# Peripherals.net
KiCad netlist of a schematic drawn in Altium Designer
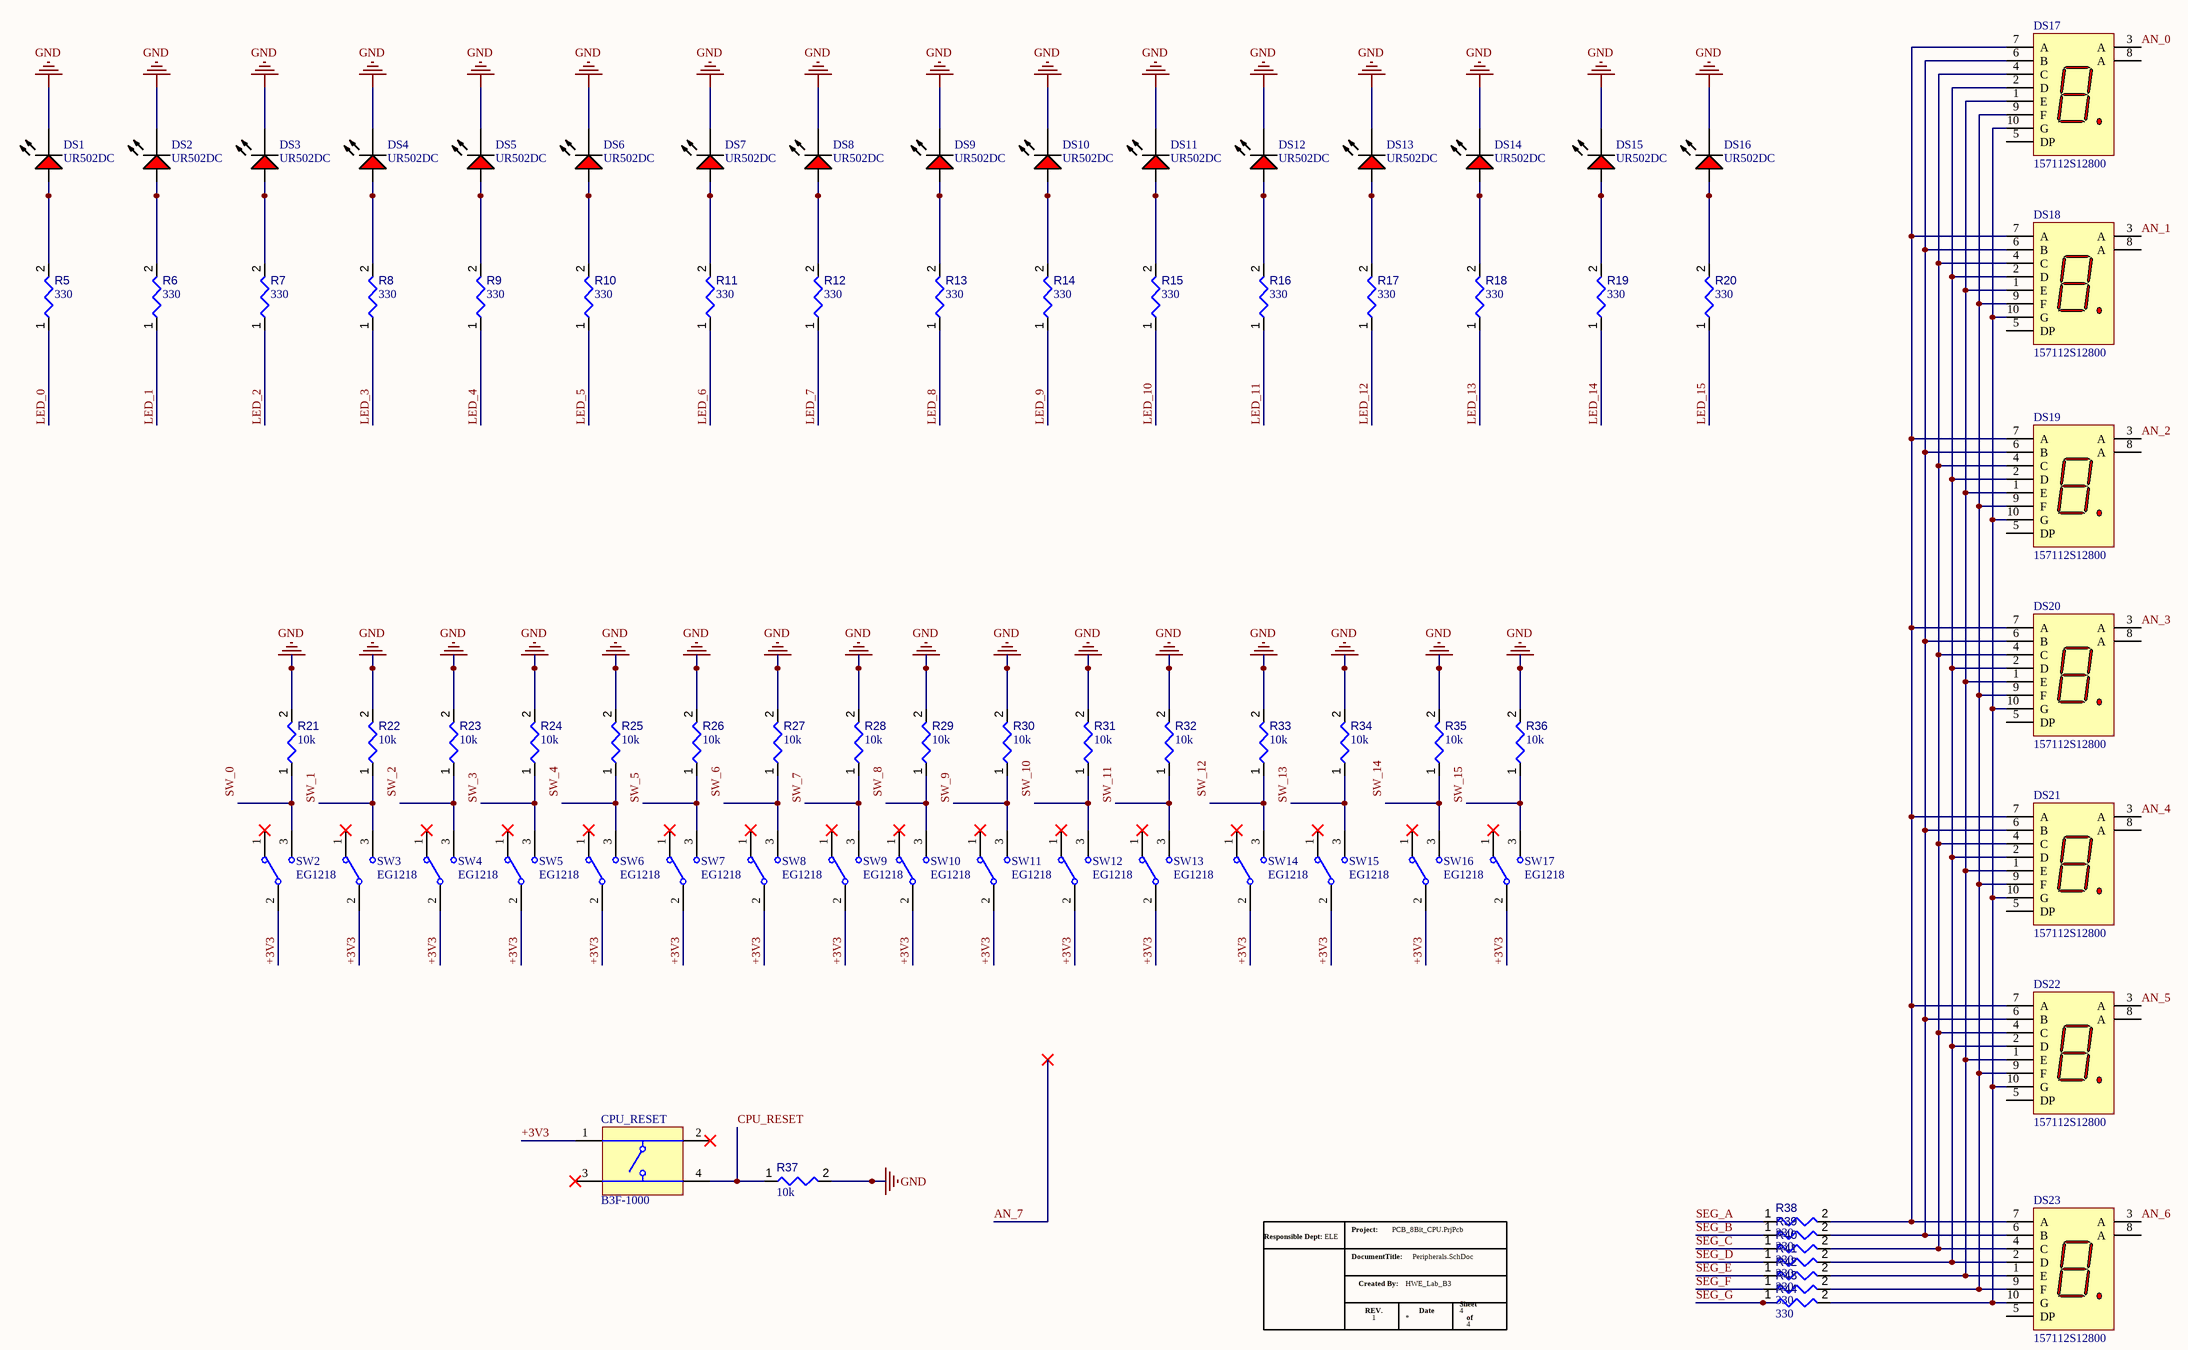
[diagram p0: Peripherals.SchDoc]

(export (version "E")
  (design (tool "Eeschema 10.0.6"))
  (components
    (comp (ref "CPU_RESET")
      (value "B3F-1000")
      (footprint "OMRON-B3F-1000-4_V")
      (description "Tactile Switch, SPST-NO, 0.05 A, 5 to 24 V, -25 to 70 degC, 4-Pin THD, RoHS, Bulk")
      (libsource (lib "Altium Content Vault") (part "SW-SPST-4_A"))
    )
    (comp (ref "DS1")
      (value "UR502DC")
      (footprint "CGX-UR502DC")
      (description "Red LED, 80 mW, 30 mA, -25 to 85 degC, 2-Pin THD")
      (fields (field (name "POWER") "80mW") (field (name "MANUFACTURER") "Shenzhen CGX"))
      (libsource (lib "MD RUHUL KUDDUS SALEH") (part "LED-RED-AK-2"))
    )
    (comp (ref "DS2")
      (value "UR502DC")
      (footprint "CGX-UR502DC")
      (description "Red LED, 80 mW, 30 mA, -25 to 85 degC, 2-Pin THD")
      (fields (field (name "POWER") "80mW") (field (name "MANUFACTURER") "Shenzhen CGX"))
      (libsource (lib "MD RUHUL KUDDUS SALEH") (part "LED-RED-AK-2"))
    )
    (comp (ref "DS3")
      (value "UR502DC")
      (footprint "CGX-UR502DC")
      (description "Red LED, 80 mW, 30 mA, -25 to 85 degC, 2-Pin THD")
      (fields (field (name "POWER") "80mW") (field (name "MANUFACTURER") "Shenzhen CGX"))
      (libsource (lib "MD RUHUL KUDDUS SALEH") (part "LED-RED-AK-2"))
    )
    (comp (ref "DS4")
      (value "UR502DC")
      (footprint "CGX-UR502DC")
      (description "Red LED, 80 mW, 30 mA, -25 to 85 degC, 2-Pin THD")
      (fields (field (name "POWER") "80mW") (field (name "MANUFACTURER") "Shenzhen CGX"))
      (libsource (lib "MD RUHUL KUDDUS SALEH") (part "LED-RED-AK-2"))
    )
    (comp (ref "DS5")
      (value "UR502DC")
      (footprint "CGX-UR502DC")
      (description "Red LED, 80 mW, 30 mA, -25 to 85 degC, 2-Pin THD")
      (fields (field (name "POWER") "80mW") (field (name "MANUFACTURER") "Shenzhen CGX"))
      (libsource (lib "MD RUHUL KUDDUS SALEH") (part "LED-RED-AK-2"))
    )
    (comp (ref "DS6")
      (value "UR502DC")
      (footprint "CGX-UR502DC")
      (description "Red LED, 80 mW, 30 mA, -25 to 85 degC, 2-Pin THD")
      (fields (field (name "POWER") "80mW") (field (name "MANUFACTURER") "Shenzhen CGX"))
      (libsource (lib "MD RUHUL KUDDUS SALEH") (part "LED-RED-AK-2"))
    )
    (comp (ref "DS7")
      (value "UR502DC")
      (footprint "CGX-UR502DC")
      (description "Red LED, 80 mW, 30 mA, -25 to 85 degC, 2-Pin THD")
      (fields (field (name "POWER") "80mW") (field (name "MANUFACTURER") "Shenzhen CGX"))
      (libsource (lib "MD RUHUL KUDDUS SALEH") (part "LED-RED-AK-2"))
    )
    (comp (ref "DS8")
      (value "UR502DC")
      (footprint "CGX-UR502DC")
      (description "Red LED, 80 mW, 30 mA, -25 to 85 degC, 2-Pin THD")
      (fields (field (name "POWER") "80mW") (field (name "MANUFACTURER") "Shenzhen CGX"))
      (libsource (lib "MD RUHUL KUDDUS SALEH") (part "LED-RED-AK-2"))
    )
    (comp (ref "DS9")
      (value "UR502DC")
      (footprint "CGX-UR502DC")
      (description "Red LED, 80 mW, 30 mA, -25 to 85 degC, 2-Pin THD")
      (fields (field (name "POWER") "80mW") (field (name "MANUFACTURER") "Shenzhen CGX"))
      (libsource (lib "MD RUHUL KUDDUS SALEH") (part "LED-RED-AK-2"))
    )
    (comp (ref "DS10")
      (value "UR502DC")
      (footprint "CGX-UR502DC")
      (description "Red LED, 80 mW, 30 mA, -25 to 85 degC, 2-Pin THD")
      (fields (field (name "POWER") "80mW") (field (name "MANUFACTURER") "Shenzhen CGX"))
      (libsource (lib "MD RUHUL KUDDUS SALEH") (part "LED-RED-AK-2"))
    )
    (comp (ref "DS11")
      (value "UR502DC")
      (footprint "CGX-UR502DC")
      (description "Red LED, 80 mW, 30 mA, -25 to 85 degC, 2-Pin THD")
      (fields (field (name "POWER") "80mW") (field (name "MANUFACTURER") "Shenzhen CGX"))
      (libsource (lib "MD RUHUL KUDDUS SALEH") (part "LED-RED-AK-2"))
    )
    (comp (ref "DS12")
      (value "UR502DC")
      (footprint "CGX-UR502DC")
      (description "Red LED, 80 mW, 30 mA, -25 to 85 degC, 2-Pin THD")
      (fields (field (name "POWER") "80mW") (field (name "MANUFACTURER") "Shenzhen CGX"))
      (libsource (lib "MD RUHUL KUDDUS SALEH") (part "LED-RED-AK-2"))
    )
    (comp (ref "DS13")
      (value "UR502DC")
      (footprint "CGX-UR502DC")
      (description "Red LED, 80 mW, 30 mA, -25 to 85 degC, 2-Pin THD")
      (fields (field (name "POWER") "80mW") (field (name "MANUFACTURER") "Shenzhen CGX"))
      (libsource (lib "MD RUHUL KUDDUS SALEH") (part "LED-RED-AK-2"))
    )
    (comp (ref "DS14")
      (value "UR502DC")
      (footprint "CGX-UR502DC")
      (description "Red LED, 80 mW, 30 mA, -25 to 85 degC, 2-Pin THD")
      (fields (field (name "POWER") "80mW") (field (name "MANUFACTURER") "Shenzhen CGX"))
      (libsource (lib "MD RUHUL KUDDUS SALEH") (part "LED-RED-AK-2"))
    )
    (comp (ref "DS15")
      (value "UR502DC")
      (footprint "CGX-UR502DC")
      (description "Red LED, 80 mW, 30 mA, -25 to 85 degC, 2-Pin THD")
      (fields (field (name "POWER") "80mW") (field (name "MANUFACTURER") "Shenzhen CGX"))
      (libsource (lib "MD RUHUL KUDDUS SALEH") (part "LED-RED-AK-2"))
    )
    (comp (ref "DS16")
      (value "UR502DC")
      (footprint "CGX-UR502DC")
      (description "Red LED, 80 mW, 30 mA, -25 to 85 degC, 2-Pin THD")
      (fields (field (name "POWER") "80mW") (field (name "MANUFACTURER") "Shenzhen CGX"))
      (libsource (lib "MD RUHUL KUDDUS SALEH") (part "LED-RED-AK-2"))
    )
    (comp (ref "DS17")
      (value "157112S12800")
      (footprint "WL-S7DS_L12W7.3H3.75")
      (description "7-Seg Display, Comm Anode, Super Red Rohs Compliant: Yes")
      (libsource (lib "Altium Content Vault") (part "7 Segments_Red_CA_type 1"))
    )
    (comp (ref "DS18")
      (value "157112S12800")
      (footprint "WL-S7DS_L12W7.3H3.75")
      (description "7-Seg Display, Comm Anode, Super Red Rohs Compliant: Yes")
      (libsource (lib "Altium Content Vault") (part "7 Segments_Red_CA_type 1"))
    )
    (comp (ref "DS19")
      (value "157112S12800")
      (footprint "WL-S7DS_L12W7.3H3.75")
      (description "7-Seg Display, Comm Anode, Super Red Rohs Compliant: Yes")
      (libsource (lib "Altium Content Vault") (part "7 Segments_Red_CA_type 1"))
    )
    (comp (ref "DS20")
      (value "157112S12800")
      (footprint "WL-S7DS_L12W7.3H3.75")
      (description "7-Seg Display, Comm Anode, Super Red Rohs Compliant: Yes")
      (libsource (lib "Altium Content Vault") (part "7 Segments_Red_CA_type 1"))
    )
    (comp (ref "DS21")
      (value "157112S12800")
      (footprint "WL-S7DS_L12W7.3H3.75")
      (description "7-Seg Display, Comm Anode, Super Red Rohs Compliant: Yes")
      (libsource (lib "Altium Content Vault") (part "7 Segments_Red_CA_type 1"))
    )
    (comp (ref "DS22")
      (value "157112S12800")
      (footprint "WL-S7DS_L12W7.3H3.75")
      (description "7-Seg Display, Comm Anode, Super Red Rohs Compliant: Yes")
      (libsource (lib "Altium Content Vault") (part "7 Segments_Red_CA_type 1"))
    )
    (comp (ref "DS23")
      (value "157112S12800")
      (footprint "WL-S7DS_L12W7.3H3.75")
      (description "7-Seg Display, Comm Anode, Super Red Rohs Compliant: Yes")
      (libsource (lib "Altium Content Vault") (part "7 Segments_Red_CA_type 1"))
    )
    (comp (ref "R5")
      (value "330")
      (footprint "RESC0402(1005)_L")
      (description "Chip Resistor, 330 Ohms, +/-5 %, 63 mW, -55 to 155 degC, 0402")
      (fields (field (name "POWER") "63mW") (field (name "TOLERANCE") "5%"))
      (libsource (lib "MD RUHUL KUDDUS SALEH") (part "RES-2"))
    )
    (comp (ref "R6")
      (value "330")
      (footprint "RESC0402(1005)_L")
      (description "Chip Resistor, 330 Ohms, +/-5 %, 63 mW, -55 to 155 degC, 0402")
      (fields (field (name "POWER") "63mW") (field (name "TOLERANCE") "5%"))
      (libsource (lib "MD RUHUL KUDDUS SALEH") (part "RES-2"))
    )
    (comp (ref "R7")
      (value "330")
      (footprint "RESC0402(1005)_L")
      (description "Chip Resistor, 330 Ohms, +/-5 %, 63 mW, -55 to 155 degC, 0402")
      (fields (field (name "POWER") "63mW") (field (name "TOLERANCE") "5%"))
      (libsource (lib "MD RUHUL KUDDUS SALEH") (part "RES-2"))
    )
    (comp (ref "R8")
      (value "330")
      (footprint "RESC0402(1005)_L")
      (description "Chip Resistor, 330 Ohms, +/-5 %, 63 mW, -55 to 155 degC, 0402")
      (fields (field (name "POWER") "63mW") (field (name "TOLERANCE") "5%"))
      (libsource (lib "MD RUHUL KUDDUS SALEH") (part "RES-2"))
    )
    (comp (ref "R9")
      (value "330")
      (footprint "RESC0402(1005)_L")
      (description "Chip Resistor, 330 Ohms, +/-5 %, 63 mW, -55 to 155 degC, 0402")
      (fields (field (name "POWER") "63mW") (field (name "TOLERANCE") "5%"))
      (libsource (lib "MD RUHUL KUDDUS SALEH") (part "RES-2"))
    )
    (comp (ref "R10")
      (value "330")
      (footprint "RESC0402(1005)_L")
      (description "Chip Resistor, 330 Ohms, +/-5 %, 63 mW, -55 to 155 degC, 0402")
      (fields (field (name "POWER") "63mW") (field (name "TOLERANCE") "5%"))
      (libsource (lib "MD RUHUL KUDDUS SALEH") (part "RES-2"))
    )
    (comp (ref "R11")
      (value "330")
      (footprint "RESC0402(1005)_L")
      (description "Chip Resistor, 330 Ohms, +/-5 %, 63 mW, -55 to 155 degC, 0402")
      (fields (field (name "POWER") "63mW") (field (name "TOLERANCE") "5%"))
      (libsource (lib "MD RUHUL KUDDUS SALEH") (part "RES-2"))
    )
    (comp (ref "R12")
      (value "330")
      (footprint "RESC0402(1005)_L")
      (description "Chip Resistor, 330 Ohms, +/-5 %, 63 mW, -55 to 155 degC, 0402")
      (fields (field (name "POWER") "63mW") (field (name "TOLERANCE") "5%"))
      (libsource (lib "MD RUHUL KUDDUS SALEH") (part "RES-2"))
    )
    (comp (ref "R13")
      (value "330")
      (footprint "RESC0402(1005)_L")
      (description "Chip Resistor, 330 Ohms, +/-5 %, 63 mW, -55 to 155 degC, 0402")
      (fields (field (name "POWER") "63mW") (field (name "TOLERANCE") "5%"))
      (libsource (lib "MD RUHUL KUDDUS SALEH") (part "RES-2"))
    )
    (comp (ref "R14")
      (value "330")
      (footprint "RESC0402(1005)_L")
      (description "Chip Resistor, 330 Ohms, +/-5 %, 63 mW, -55 to 155 degC, 0402")
      (fields (field (name "POWER") "63mW") (field (name "TOLERANCE") "5%"))
      (libsource (lib "MD RUHUL KUDDUS SALEH") (part "RES-2"))
    )
    (comp (ref "R15")
      (value "330")
      (footprint "RESC0402(1005)_L")
      (description "Chip Resistor, 330 Ohms, +/-5 %, 63 mW, -55 to 155 degC, 0402")
      (fields (field (name "POWER") "63mW") (field (name "TOLERANCE") "5%"))
      (libsource (lib "MD RUHUL KUDDUS SALEH") (part "RES-2"))
    )
    (comp (ref "R16")
      (value "330")
      (footprint "RESC0402(1005)_L")
      (description "Chip Resistor, 330 Ohms, +/-5 %, 63 mW, -55 to 155 degC, 0402")
      (fields (field (name "POWER") "63mW") (field (name "TOLERANCE") "5%"))
      (libsource (lib "MD RUHUL KUDDUS SALEH") (part "RES-2"))
    )
    (comp (ref "R17")
      (value "330")
      (footprint "RESC0402(1005)_L")
      (description "Chip Resistor, 330 Ohms, +/-5 %, 63 mW, -55 to 155 degC, 0402")
      (fields (field (name "POWER") "63mW") (field (name "TOLERANCE") "5%"))
      (libsource (lib "MD RUHUL KUDDUS SALEH") (part "RES-2"))
    )
    (comp (ref "R18")
      (value "330")
      (footprint "RESC0402(1005)_L")
      (description "Chip Resistor, 330 Ohms, +/-5 %, 63 mW, -55 to 155 degC, 0402")
      (fields (field (name "POWER") "63mW") (field (name "TOLERANCE") "5%"))
      (libsource (lib "MD RUHUL KUDDUS SALEH") (part "RES-2"))
    )
    (comp (ref "R19")
      (value "330")
      (footprint "RESC0402(1005)_L")
      (description "Chip Resistor, 330 Ohms, +/-5 %, 63 mW, -55 to 155 degC, 0402")
      (fields (field (name "POWER") "63mW") (field (name "TOLERANCE") "5%"))
      (libsource (lib "MD RUHUL KUDDUS SALEH") (part "RES-2"))
    )
    (comp (ref "R20")
      (value "330")
      (footprint "RESC0402(1005)_L")
      (description "Chip Resistor, 330 Ohms, +/-5 %, 63 mW, -55 to 155 degC, 0402")
      (fields (field (name "POWER") "63mW") (field (name "TOLERANCE") "5%"))
      (libsource (lib "MD RUHUL KUDDUS SALEH") (part "RES-2"))
    )
    (comp (ref "R21")
      (value "10k")
      (footprint "RESC0402(1005)_L")
      (description "10K 0.063W 1% 0402 (1005 Metric)  SMD")
      (fields (field (name "POWER") "63mW") (field (name "TOLERANCE") "1%"))
      (libsource (lib "MD RUHUL KUDDUS SALEH") (part "10KR2F"))
    )
    (comp (ref "R22")
      (value "10k")
      (footprint "RESC0402(1005)_L")
      (description "10K 0.063W 1% 0402 (1005 Metric)  SMD")
      (fields (field (name "POWER") "63mW") (field (name "TOLERANCE") "1%"))
      (libsource (lib "MD RUHUL KUDDUS SALEH") (part "10KR2F"))
    )
    (comp (ref "R23")
      (value "10k")
      (footprint "RESC0402(1005)_L")
      (description "10K 0.063W 1% 0402 (1005 Metric)  SMD")
      (fields (field (name "POWER") "63mW") (field (name "TOLERANCE") "1%"))
      (libsource (lib "MD RUHUL KUDDUS SALEH") (part "10KR2F"))
    )
    (comp (ref "R24")
      (value "10k")
      (footprint "RESC0402(1005)_L")
      (description "10K 0.063W 1% 0402 (1005 Metric)  SMD")
      (fields (field (name "POWER") "63mW") (field (name "TOLERANCE") "1%"))
      (libsource (lib "MD RUHUL KUDDUS SALEH") (part "10KR2F"))
    )
    (comp (ref "R25")
      (value "10k")
      (footprint "RESC0402(1005)_L")
      (description "10K 0.063W 1% 0402 (1005 Metric)  SMD")
      (fields (field (name "POWER") "63mW") (field (name "TOLERANCE") "1%"))
      (libsource (lib "MD RUHUL KUDDUS SALEH") (part "10KR2F"))
    )
    (comp (ref "R26")
      (value "10k")
      (footprint "RESC0402(1005)_L")
      (description "10K 0.063W 1% 0402 (1005 Metric)  SMD")
      (fields (field (name "POWER") "63mW") (field (name "TOLERANCE") "1%"))
      (libsource (lib "MD RUHUL KUDDUS SALEH") (part "10KR2F"))
    )
    (comp (ref "R27")
      (value "10k")
      (footprint "RESC0402(1005)_L")
      (description "10K 0.063W 1% 0402 (1005 Metric)  SMD")
      (fields (field (name "POWER") "63mW") (field (name "TOLERANCE") "1%"))
      (libsource (lib "MD RUHUL KUDDUS SALEH") (part "10KR2F"))
    )
    (comp (ref "R28")
      (value "10k")
      (footprint "RESC0402(1005)_L")
      (description "10K 0.063W 1% 0402 (1005 Metric)  SMD")
      (fields (field (name "POWER") "63mW") (field (name "TOLERANCE") "1%"))
      (libsource (lib "MD RUHUL KUDDUS SALEH") (part "10KR2F"))
    )
    (comp (ref "R29")
      (value "10k")
      (footprint "RESC0402(1005)_L")
      (description "10K 0.063W 1% 0402 (1005 Metric)  SMD")
      (fields (field (name "POWER") "63mW") (field (name "TOLERANCE") "1%"))
      (libsource (lib "MD RUHUL KUDDUS SALEH") (part "10KR2F"))
    )
    (comp (ref "R30")
      (value "10k")
      (footprint "RESC0402(1005)_L")
      (description "10K 0.063W 1% 0402 (1005 Metric)  SMD")
      (fields (field (name "POWER") "63mW") (field (name "TOLERANCE") "1%"))
      (libsource (lib "MD RUHUL KUDDUS SALEH") (part "10KR2F"))
    )
    (comp (ref "R31")
      (value "10k")
      (footprint "RESC0402(1005)_L")
      (description "10K 0.063W 1% 0402 (1005 Metric)  SMD")
      (fields (field (name "POWER") "63mW") (field (name "TOLERANCE") "1%"))
      (libsource (lib "MD RUHUL KUDDUS SALEH") (part "10KR2F"))
    )
    (comp (ref "R32")
      (value "10k")
      (footprint "RESC0402(1005)_L")
      (description "10K 0.063W 1% 0402 (1005 Metric)  SMD")
      (fields (field (name "POWER") "63mW") (field (name "TOLERANCE") "1%"))
      (libsource (lib "MD RUHUL KUDDUS SALEH") (part "10KR2F"))
    )
    (comp (ref "R33")
      (value "10k")
      (footprint "RESC0402(1005)_L")
      (description "10K 0.063W 1% 0402 (1005 Metric)  SMD")
      (fields (field (name "POWER") "63mW") (field (name "TOLERANCE") "1%"))
      (libsource (lib "MD RUHUL KUDDUS SALEH") (part "10KR2F"))
    )
    (comp (ref "R34")
      (value "10k")
      (footprint "RESC0402(1005)_L")
      (description "10K 0.063W 1% 0402 (1005 Metric)  SMD")
      (fields (field (name "POWER") "63mW") (field (name "TOLERANCE") "1%"))
      (libsource (lib "MD RUHUL KUDDUS SALEH") (part "10KR2F"))
    )
    (comp (ref "R35")
      (value "10k")
      (footprint "RESC0402(1005)_L")
      (description "10K 0.063W 1% 0402 (1005 Metric)  SMD")
      (fields (field (name "POWER") "63mW") (field (name "TOLERANCE") "1%"))
      (libsource (lib "MD RUHUL KUDDUS SALEH") (part "10KR2F"))
    )
    (comp (ref "R36")
      (value "10k")
      (footprint "RESC0402(1005)_L")
      (description "10K 0.063W 1% 0402 (1005 Metric)  SMD")
      (fields (field (name "POWER") "63mW") (field (name "TOLERANCE") "1%"))
      (libsource (lib "MD RUHUL KUDDUS SALEH") (part "10KR2F"))
    )
    (comp (ref "R37")
      (value "10k")
      (footprint "RESC0402(1005)_L")
      (description "10K 0.063W 1% 0402 (1005 Metric)  SMD")
      (fields (field (name "POWER") "63mW") (field (name "TOLERANCE") "1%"))
      (libsource (lib "MD RUHUL KUDDUS SALEH") (part "10KR2F"))
    )
    (comp (ref "R38")
      (value "330")
      (footprint "RESC0402(1005)_L")
      (description "Chip Resistor, 330 Ohms, +/-5 %, 63 mW, -55 to 155 degC, 0402")
      (fields (field (name "POWER") "63mW") (field (name "TOLERANCE") "5%"))
      (libsource (lib "MD RUHUL KUDDUS SALEH") (part "RES-2"))
    )
    (comp (ref "R39")
      (value "330")
      (footprint "RESC0402(1005)_L")
      (description "Chip Resistor, 330 Ohms, +/-5 %, 63 mW, -55 to 155 degC, 0402")
      (fields (field (name "POWER") "63mW") (field (name "TOLERANCE") "5%"))
      (libsource (lib "MD RUHUL KUDDUS SALEH") (part "RES-2"))
    )
    (comp (ref "R40")
      (value "330")
      (footprint "RESC0402(1005)_L")
      (description "Chip Resistor, 330 Ohms, +/-5 %, 63 mW, -55 to 155 degC, 0402")
      (fields (field (name "POWER") "63mW") (field (name "TOLERANCE") "5%"))
      (libsource (lib "MD RUHUL KUDDUS SALEH") (part "RES-2"))
    )
    (comp (ref "R41")
      (value "330")
      (footprint "RESC0402(1005)_L")
      (description "Chip Resistor, 330 Ohms, +/-5 %, 63 mW, -55 to 155 degC, 0402")
      (fields (field (name "POWER") "63mW") (field (name "TOLERANCE") "5%"))
      (libsource (lib "MD RUHUL KUDDUS SALEH") (part "RES-2"))
    )
    (comp (ref "R42")
      (value "330")
      (footprint "RESC0402(1005)_L")
      (description "Chip Resistor, 330 Ohms, +/-5 %, 63 mW, -55 to 155 degC, 0402")
      (fields (field (name "POWER") "63mW") (field (name "TOLERANCE") "5%"))
      (libsource (lib "MD RUHUL KUDDUS SALEH") (part "RES-2"))
    )
    (comp (ref "R43")
      (value "330")
      (footprint "RESC0402(1005)_L")
      (description "Chip Resistor, 330 Ohms, +/-5 %, 63 mW, -55 to 155 degC, 0402")
      (fields (field (name "POWER") "63mW") (field (name "TOLERANCE") "5%"))
      (libsource (lib "MD RUHUL KUDDUS SALEH") (part "RES-2"))
    )
    (comp (ref "R44")
      (value "330")
      (footprint "RESC0402(1005)_L")
      (description "Chip Resistor, 330 Ohms, +/-5 %, 63 mW, -55 to 155 degC, 0402")
      (fields (field (name "POWER") "63mW") (field (name "TOLERANCE") "5%"))
      (libsource (lib "MD RUHUL KUDDUS SALEH") (part "RES-2"))
    )
    (comp (ref "SW2")
      (value "EG1218")
      (footprint "ESWI-EG1218_V")
      (description "Slide Switch, SPDT, 500 V, -20 to 70 degC, 3-Pin THD, RoHS, Bulk")
      (fields (field (name "MANUFACTURER") "E-Switch"))
      (libsource (lib "MD RUHUL KUDDUS SALEH") (part "SW-SPDT-3_B"))
    )
    (comp (ref "SW3")
      (value "EG1218")
      (footprint "ESWI-EG1218_V")
      (description "Slide Switch, SPDT, 500 V, -20 to 70 degC, 3-Pin THD, RoHS, Bulk")
      (fields (field (name "MANUFACTURER") "E-Switch"))
      (libsource (lib "MD RUHUL KUDDUS SALEH") (part "SW-SPDT-3_B"))
    )
    (comp (ref "SW4")
      (value "EG1218")
      (footprint "ESWI-EG1218_V")
      (description "Slide Switch, SPDT, 500 V, -20 to 70 degC, 3-Pin THD, RoHS, Bulk")
      (fields (field (name "MANUFACTURER") "E-Switch"))
      (libsource (lib "MD RUHUL KUDDUS SALEH") (part "SW-SPDT-3_B"))
    )
    (comp (ref "SW5")
      (value "EG1218")
      (footprint "ESWI-EG1218_V")
      (description "Slide Switch, SPDT, 500 V, -20 to 70 degC, 3-Pin THD, RoHS, Bulk")
      (fields (field (name "MANUFACTURER") "E-Switch"))
      (libsource (lib "MD RUHUL KUDDUS SALEH") (part "SW-SPDT-3_B"))
    )
    (comp (ref "SW6")
      (value "EG1218")
      (footprint "ESWI-EG1218_V")
      (description "Slide Switch, SPDT, 500 V, -20 to 70 degC, 3-Pin THD, RoHS, Bulk")
      (fields (field (name "MANUFACTURER") "E-Switch"))
      (libsource (lib "MD RUHUL KUDDUS SALEH") (part "SW-SPDT-3_B"))
    )
    (comp (ref "SW7")
      (value "EG1218")
      (footprint "ESWI-EG1218_V")
      (description "Slide Switch, SPDT, 500 V, -20 to 70 degC, 3-Pin THD, RoHS, Bulk")
      (fields (field (name "MANUFACTURER") "E-Switch"))
      (libsource (lib "MD RUHUL KUDDUS SALEH") (part "SW-SPDT-3_B"))
    )
    (comp (ref "SW8")
      (value "EG1218")
      (footprint "ESWI-EG1218_V")
      (description "Slide Switch, SPDT, 500 V, -20 to 70 degC, 3-Pin THD, RoHS, Bulk")
      (fields (field (name "MANUFACTURER") "E-Switch"))
      (libsource (lib "MD RUHUL KUDDUS SALEH") (part "SW-SPDT-3_B"))
    )
    (comp (ref "SW9")
      (value "EG1218")
      (footprint "ESWI-EG1218_V")
      (description "Slide Switch, SPDT, 500 V, -20 to 70 degC, 3-Pin THD, RoHS, Bulk")
      (fields (field (name "MANUFACTURER") "E-Switch"))
      (libsource (lib "MD RUHUL KUDDUS SALEH") (part "SW-SPDT-3_B"))
    )
    (comp (ref "SW10")
      (value "EG1218")
      (footprint "ESWI-EG1218_V")
      (description "Slide Switch, SPDT, 500 V, -20 to 70 degC, 3-Pin THD, RoHS, Bulk")
      (fields (field (name "MANUFACTURER") "E-Switch"))
      (libsource (lib "MD RUHUL KUDDUS SALEH") (part "SW-SPDT-3_B"))
    )
    (comp (ref "SW11")
      (value "EG1218")
      (footprint "ESWI-EG1218_V")
      (description "Slide Switch, SPDT, 500 V, -20 to 70 degC, 3-Pin THD, RoHS, Bulk")
      (fields (field (name "MANUFACTURER") "E-Switch"))
      (libsource (lib "MD RUHUL KUDDUS SALEH") (part "SW-SPDT-3_B"))
    )
    (comp (ref "SW12")
      (value "EG1218")
      (footprint "ESWI-EG1218_V")
      (description "Slide Switch, SPDT, 500 V, -20 to 70 degC, 3-Pin THD, RoHS, Bulk")
      (fields (field (name "MANUFACTURER") "E-Switch"))
      (libsource (lib "MD RUHUL KUDDUS SALEH") (part "SW-SPDT-3_B"))
    )
    (comp (ref "SW13")
      (value "EG1218")
      (footprint "ESWI-EG1218_V")
      (description "Slide Switch, SPDT, 500 V, -20 to 70 degC, 3-Pin THD, RoHS, Bulk")
      (fields (field (name "MANUFACTURER") "E-Switch"))
      (libsource (lib "MD RUHUL KUDDUS SALEH") (part "SW-SPDT-3_B"))
    )
    (comp (ref "SW14")
      (value "EG1218")
      (footprint "ESWI-EG1218_V")
      (description "Slide Switch, SPDT, 500 V, -20 to 70 degC, 3-Pin THD, RoHS, Bulk")
      (fields (field (name "MANUFACTURER") "E-Switch"))
      (libsource (lib "MD RUHUL KUDDUS SALEH") (part "SW-SPDT-3_B"))
    )
    (comp (ref "SW15")
      (value "EG1218")
      (footprint "ESWI-EG1218_V")
      (description "Slide Switch, SPDT, 500 V, -20 to 70 degC, 3-Pin THD, RoHS, Bulk")
      (fields (field (name "MANUFACTURER") "E-Switch"))
      (libsource (lib "MD RUHUL KUDDUS SALEH") (part "SW-SPDT-3_B"))
    )
    (comp (ref "SW16")
      (value "EG1218")
      (footprint "ESWI-EG1218_V")
      (description "Slide Switch, SPDT, 500 V, -20 to 70 degC, 3-Pin THD, RoHS, Bulk")
      (fields (field (name "MANUFACTURER") "E-Switch"))
      (libsource (lib "MD RUHUL KUDDUS SALEH") (part "SW-SPDT-3_B"))
    )
    (comp (ref "SW17")
      (value "EG1218")
      (footprint "ESWI-EG1218_V")
      (description "Slide Switch, SPDT, 500 V, -20 to 70 degC, 3-Pin THD, RoHS, Bulk")
      (fields (field (name "MANUFACTURER") "E-Switch"))
      (libsource (lib "MD RUHUL KUDDUS SALEH") (part "SW-SPDT-3_B"))
    )
  )
  (nets
    (net (code "1") (name "/  SW_0") (class "Default")
      (node (ref "R21") (pin "1") (pinfunction "1_1") (pintype "passive"))
      (node (ref "SW2") (pin "3") (pinfunction "3_3") (pintype "passive"))
    )
    (net (code "2") (name "/  SW_2") (class "Default")
      (node (ref "R23") (pin "1") (pinfunction "1_1") (pintype "passive"))
      (node (ref "SW4") (pin "3") (pinfunction "3_3") (pintype "passive"))
    )
    (net (code "3") (name "/  SW_4") (class "Default")
      (node (ref "R25") (pin "1") (pinfunction "1_1") (pintype "passive"))
      (node (ref "SW6") (pin "3") (pinfunction "3_3") (pintype "passive"))
    )
    (net (code "4") (name "/  SW_6") (class "Default")
      (node (ref "R27") (pin "1") (pinfunction "1_1") (pintype "passive"))
      (node (ref "SW8") (pin "3") (pinfunction "3_3") (pintype "passive"))
    )
    (net (code "5") (name "/  SW_8") (class "Default")
      (node (ref "R29") (pin "1") (pinfunction "1_1") (pintype "passive"))
      (node (ref "SW10") (pin "3") (pinfunction "3_3") (pintype "passive"))
    )
    (net (code "6") (name "/  SW_10") (class "Default")
      (node (ref "R31") (pin "1") (pinfunction "1_1") (pintype "passive"))
      (node (ref "SW12") (pin "3") (pinfunction "3_3") (pintype "passive"))
    )
    (net (code "7") (name "/  SW_12") (class "Default")
      (node (ref "R33") (pin "1") (pinfunction "1_1") (pintype "passive"))
      (node (ref "SW14") (pin "3") (pinfunction "3_3") (pintype "passive"))
    )
    (net (code "8") (name "/  SW_14") (class "Default")
      (node (ref "R35") (pin "1") (pinfunction "1_1") (pintype "passive"))
      (node (ref "SW16") (pin "3") (pinfunction "3_3") (pintype "passive"))
    )
    (net (code "9") (name "/+3V3") (class "Default")
      (node (ref "CPU_RESET") (pin "1") (pinfunction "1_1") (pintype "passive"))
      (node (ref "SW10") (pin "2") (pinfunction "COM_2") (pintype "passive"))
      (node (ref "SW11") (pin "2") (pinfunction "COM_2") (pintype "passive"))
      (node (ref "SW12") (pin "2") (pinfunction "COM_2") (pintype "passive"))
      (node (ref "SW13") (pin "2") (pinfunction "COM_2") (pintype "passive"))
      (node (ref "SW14") (pin "2") (pinfunction "COM_2") (pintype "passive"))
      (node (ref "SW15") (pin "2") (pinfunction "COM_2") (pintype "passive"))
      (node (ref "SW16") (pin "2") (pinfunction "COM_2") (pintype "passive"))
      (node (ref "SW17") (pin "2") (pinfunction "COM_2") (pintype "passive"))
      (node (ref "SW2") (pin "2") (pinfunction "COM_2") (pintype "passive"))
      (node (ref "SW3") (pin "2") (pinfunction "COM_2") (pintype "passive"))
      (node (ref "SW4") (pin "2") (pinfunction "COM_2") (pintype "passive"))
      (node (ref "SW5") (pin "2") (pinfunction "COM_2") (pintype "passive"))
      (node (ref "SW6") (pin "2") (pinfunction "COM_2") (pintype "passive"))
      (node (ref "SW7") (pin "2") (pinfunction "COM_2") (pintype "passive"))
      (node (ref "SW8") (pin "2") (pinfunction "COM_2") (pintype "passive"))
      (node (ref "SW9") (pin "2") (pinfunction "COM_2") (pintype "passive"))
    )
    (net (code "10") (name "/AN_0") (class "Default")
      (node (ref "DS17") (pin "3") (pinfunction "A_3") (pintype "passive"))
    )
    (net (code "11") (name "/AN_1") (class "Default")
      (node (ref "DS18") (pin "3") (pinfunction "A_3") (pintype "passive"))
    )
    (net (code "12") (name "/AN_2") (class "Default")
      (node (ref "DS19") (pin "3") (pinfunction "A_3") (pintype "passive"))
    )
    (net (code "13") (name "/AN_3") (class "Default")
      (node (ref "DS20") (pin "3") (pinfunction "A_3") (pintype "passive"))
    )
    (net (code "14") (name "/AN_4") (class "Default")
      (node (ref "DS21") (pin "3") (pinfunction "A_3") (pintype "passive"))
    )
    (net (code "15") (name "/AN_5") (class "Default")
      (node (ref "DS22") (pin "3") (pinfunction "A_3") (pintype "passive"))
    )
    (net (code "16") (name "/AN_6") (class "Default")
      (node (ref "DS23") (pin "3") (pinfunction "A_3") (pintype "passive"))
    )
    (net (code "18") (name "/CPU_RESET") (class "Default")
      (node (ref "CPU_RESET") (pin "4") (pinfunction "4_4") (pintype "passive"))
      (node (ref "R37") (pin "1") (pinfunction "1_1") (pintype "passive"))
    )
    (net (code "19") (name "/LED_0") (class "Default")
      (node (ref "R5") (pin "1") (pinfunction "1_1") (pintype "passive"))
    )
    (net (code "20") (name "/LED_1") (class "Default")
      (node (ref "R6") (pin "1") (pinfunction "1_1") (pintype "passive"))
    )
    (net (code "21") (name "/LED_2") (class "Default")
      (node (ref "R7") (pin "1") (pinfunction "1_1") (pintype "passive"))
    )
    (net (code "22") (name "/LED_3") (class "Default")
      (node (ref "R8") (pin "1") (pinfunction "1_1") (pintype "passive"))
    )
    (net (code "23") (name "/LED_4") (class "Default")
      (node (ref "R9") (pin "1") (pinfunction "1_1") (pintype "passive"))
    )
    (net (code "24") (name "/LED_5") (class "Default")
      (node (ref "R10") (pin "1") (pinfunction "1_1") (pintype "passive"))
    )
    (net (code "25") (name "/LED_6") (class "Default")
      (node (ref "R11") (pin "1") (pinfunction "1_1") (pintype "passive"))
    )
    (net (code "26") (name "/LED_7") (class "Default")
      (node (ref "R12") (pin "1") (pinfunction "1_1") (pintype "passive"))
    )
    (net (code "27") (name "/LED_8") (class "Default")
      (node (ref "R13") (pin "1") (pinfunction "1_1") (pintype "passive"))
    )
    (net (code "28") (name "/LED_9") (class "Default")
      (node (ref "R14") (pin "1") (pinfunction "1_1") (pintype "passive"))
    )
    (net (code "29") (name "/LED_10") (class "Default")
      (node (ref "R15") (pin "1") (pinfunction "1_1") (pintype "passive"))
    )
    (net (code "30") (name "/LED_11") (class "Default")
      (node (ref "R16") (pin "1") (pinfunction "1_1") (pintype "passive"))
    )
    (net (code "31") (name "/LED_12") (class "Default")
      (node (ref "R17") (pin "1") (pinfunction "1_1") (pintype "passive"))
    )
    (net (code "32") (name "/LED_13") (class "Default")
      (node (ref "R18") (pin "1") (pinfunction "1_1") (pintype "passive"))
    )
    (net (code "33") (name "/LED_14") (class "Default")
      (node (ref "R19") (pin "1") (pinfunction "1_1") (pintype "passive"))
    )
    (net (code "34") (name "/LED_15") (class "Default")
      (node (ref "R20") (pin "1") (pinfunction "1_1") (pintype "passive"))
    )
    (net (code "35") (name "/SEG_A") (class "Default")
      (node (ref "R38") (pin "1") (pinfunction "1_1") (pintype "passive"))
    )
    (net (code "36") (name "/SEG_B") (class "Default")
      (node (ref "R39") (pin "1") (pinfunction "1_1") (pintype "passive"))
    )
    (net (code "37") (name "/SEG_C") (class "Default")
      (node (ref "R40") (pin "1") (pinfunction "1_1") (pintype "passive"))
    )
    (net (code "38") (name "/SEG_D") (class "Default")
      (node (ref "R41") (pin "1") (pinfunction "1_1") (pintype "passive"))
    )
    (net (code "39") (name "/SEG_E") (class "Default")
      (node (ref "R42") (pin "1") (pinfunction "1_1") (pintype "passive"))
    )
    (net (code "40") (name "/SEG_F") (class "Default")
      (node (ref "R43") (pin "1") (pinfunction "1_1") (pintype "passive"))
    )
    (net (code "41") (name "/SEG_G") (class "Default")
      (node (ref "R44") (pin "1") (pinfunction "1_1") (pintype "passive"))
    )
    (net (code "42") (name "/SW_1") (class "Default")
      (node (ref "R22") (pin "1") (pinfunction "1_1") (pintype "passive"))
      (node (ref "SW3") (pin "3") (pinfunction "3_3") (pintype "passive"))
    )
    (net (code "43") (name "/SW_3") (class "Default")
      (node (ref "R24") (pin "1") (pinfunction "1_1") (pintype "passive"))
      (node (ref "SW5") (pin "3") (pinfunction "3_3") (pintype "passive"))
    )
    (net (code "44") (name "/SW_5") (class "Default")
      (node (ref "R26") (pin "1") (pinfunction "1_1") (pintype "passive"))
      (node (ref "SW7") (pin "3") (pinfunction "3_3") (pintype "passive"))
    )
    (net (code "45") (name "/SW_7") (class "Default")
      (node (ref "R28") (pin "1") (pinfunction "1_1") (pintype "passive"))
      (node (ref "SW9") (pin "3") (pinfunction "3_3") (pintype "passive"))
    )
    (net (code "46") (name "/SW_9") (class "Default")
      (node (ref "R30") (pin "1") (pinfunction "1_1") (pintype "passive"))
      (node (ref "SW11") (pin "3") (pinfunction "3_3") (pintype "passive"))
    )
    (net (code "47") (name "/SW_11") (class "Default")
      (node (ref "R32") (pin "1") (pinfunction "1_1") (pintype "passive"))
      (node (ref "SW13") (pin "3") (pinfunction "3_3") (pintype "passive"))
    )
    (net (code "48") (name "/SW_13") (class "Default")
      (node (ref "R34") (pin "1") (pinfunction "1_1") (pintype "passive"))
      (node (ref "SW15") (pin "3") (pinfunction "3_3") (pintype "passive"))
    )
    (net (code "49") (name "/SW_15") (class "Default")
      (node (ref "R36") (pin "1") (pinfunction "1_1") (pintype "passive"))
      (node (ref "SW17") (pin "3") (pinfunction "3_3") (pintype "passive"))
    )
    (net (code "50") (name "GND") (class "Default")
      (node (ref "DS1") (pin "2") (pinfunction "K_2") (pintype "passive"))
      (node (ref "DS10") (pin "2") (pinfunction "K_2") (pintype "passive"))
      (node (ref "DS11") (pin "2") (pinfunction "K_2") (pintype "passive"))
      (node (ref "DS12") (pin "2") (pinfunction "K_2") (pintype "passive"))
      (node (ref "DS13") (pin "2") (pinfunction "K_2") (pintype "passive"))
      (node (ref "DS14") (pin "2") (pinfunction "K_2") (pintype "passive"))
      (node (ref "DS15") (pin "2") (pinfunction "K_2") (pintype "passive"))
      (node (ref "DS16") (pin "2") (pinfunction "K_2") (pintype "passive"))
      (node (ref "DS2") (pin "2") (pinfunction "K_2") (pintype "passive"))
      (node (ref "DS3") (pin "2") (pinfunction "K_2") (pintype "passive"))
      (node (ref "DS4") (pin "2") (pinfunction "K_2") (pintype "passive"))
      (node (ref "DS5") (pin "2") (pinfunction "K_2") (pintype "passive"))
      (node (ref "DS6") (pin "2") (pinfunction "K_2") (pintype "passive"))
      (node (ref "DS7") (pin "2") (pinfunction "K_2") (pintype "passive"))
      (node (ref "DS8") (pin "2") (pinfunction "K_2") (pintype "passive"))
      (node (ref "DS9") (pin "2") (pinfunction "K_2") (pintype "passive"))
      (node (ref "R21") (pin "2") (pinfunction "2_2") (pintype "passive"))
      (node (ref "R22") (pin "2") (pinfunction "2_2") (pintype "passive"))
      (node (ref "R23") (pin "2") (pinfunction "2_2") (pintype "passive"))
      (node (ref "R24") (pin "2") (pinfunction "2_2") (pintype "passive"))
      (node (ref "R25") (pin "2") (pinfunction "2_2") (pintype "passive"))
      (node (ref "R26") (pin "2") (pinfunction "2_2") (pintype "passive"))
      (node (ref "R27") (pin "2") (pinfunction "2_2") (pintype "passive"))
      (node (ref "R28") (pin "2") (pinfunction "2_2") (pintype "passive"))
      (node (ref "R29") (pin "2") (pinfunction "2_2") (pintype "passive"))
      (node (ref "R30") (pin "2") (pinfunction "2_2") (pintype "passive"))
      (node (ref "R31") (pin "2") (pinfunction "2_2") (pintype "passive"))
      (node (ref "R32") (pin "2") (pinfunction "2_2") (pintype "passive"))
      (node (ref "R33") (pin "2") (pinfunction "2_2") (pintype "passive"))
      (node (ref "R34") (pin "2") (pinfunction "2_2") (pintype "passive"))
      (node (ref "R35") (pin "2") (pinfunction "2_2") (pintype "passive"))
      (node (ref "R36") (pin "2") (pinfunction "2_2") (pintype "passive"))
      (node (ref "R37") (pin "2") (pinfunction "2_2") (pintype "passive"))
    )
    (net (code "51") (name "Net-(DS1-A)") (class "Default")
      (node (ref "DS1") (pin "1") (pinfunction "A_1") (pintype "passive"))
      (node (ref "R5") (pin "2") (pinfunction "2_2") (pintype "passive"))
    )
    (net (code "52") (name "Net-(DS2-A)") (class "Default")
      (node (ref "DS2") (pin "1") (pinfunction "A_1") (pintype "passive"))
      (node (ref "R6") (pin "2") (pinfunction "2_2") (pintype "passive"))
    )
    (net (code "53") (name "Net-(DS3-A)") (class "Default")
      (node (ref "DS3") (pin "1") (pinfunction "A_1") (pintype "passive"))
      (node (ref "R7") (pin "2") (pinfunction "2_2") (pintype "passive"))
    )
    (net (code "54") (name "Net-(DS4-A)") (class "Default")
      (node (ref "DS4") (pin "1") (pinfunction "A_1") (pintype "passive"))
      (node (ref "R8") (pin "2") (pinfunction "2_2") (pintype "passive"))
    )
    (net (code "55") (name "Net-(DS5-A)") (class "Default")
      (node (ref "DS5") (pin "1") (pinfunction "A_1") (pintype "passive"))
      (node (ref "R9") (pin "2") (pinfunction "2_2") (pintype "passive"))
    )
    (net (code "56") (name "Net-(DS6-A)") (class "Default")
      (node (ref "DS6") (pin "1") (pinfunction "A_1") (pintype "passive"))
      (node (ref "R10") (pin "2") (pinfunction "2_2") (pintype "passive"))
    )
    (net (code "57") (name "Net-(DS7-A)") (class "Default")
      (node (ref "DS7") (pin "1") (pinfunction "A_1") (pintype "passive"))
      (node (ref "R11") (pin "2") (pinfunction "2_2") (pintype "passive"))
    )
    (net (code "58") (name "Net-(DS8-A)") (class "Default")
      (node (ref "DS8") (pin "1") (pinfunction "A_1") (pintype "passive"))
      (node (ref "R12") (pin "2") (pinfunction "2_2") (pintype "passive"))
    )
    (net (code "59") (name "Net-(DS9-A)") (class "Default")
      (node (ref "DS9") (pin "1") (pinfunction "A_1") (pintype "passive"))
      (node (ref "R13") (pin "2") (pinfunction "2_2") (pintype "passive"))
    )
    (net (code "60") (name "Net-(DS10-A)") (class "Default")
      (node (ref "DS10") (pin "1") (pinfunction "A_1") (pintype "passive"))
      (node (ref "R14") (pin "2") (pinfunction "2_2") (pintype "passive"))
    )
    (net (code "61") (name "Net-(DS11-A)") (class "Default")
      (node (ref "DS11") (pin "1") (pinfunction "A_1") (pintype "passive"))
      (node (ref "R15") (pin "2") (pinfunction "2_2") (pintype "passive"))
    )
    (net (code "62") (name "Net-(DS12-A)") (class "Default")
      (node (ref "DS12") (pin "1") (pinfunction "A_1") (pintype "passive"))
      (node (ref "R16") (pin "2") (pinfunction "2_2") (pintype "passive"))
    )
    (net (code "63") (name "Net-(DS13-A)") (class "Default")
      (node (ref "DS13") (pin "1") (pinfunction "A_1") (pintype "passive"))
      (node (ref "R17") (pin "2") (pinfunction "2_2") (pintype "passive"))
    )
    (net (code "64") (name "Net-(DS14-A)") (class "Default")
      (node (ref "DS14") (pin "1") (pinfunction "A_1") (pintype "passive"))
      (node (ref "R18") (pin "2") (pinfunction "2_2") (pintype "passive"))
    )
    (net (code "65") (name "Net-(DS15-A)") (class "Default")
      (node (ref "DS15") (pin "1") (pinfunction "A_1") (pintype "passive"))
      (node (ref "R19") (pin "2") (pinfunction "2_2") (pintype "passive"))
    )
    (net (code "66") (name "Net-(DS16-A)") (class "Default")
      (node (ref "DS16") (pin "1") (pinfunction "A_1") (pintype "passive"))
      (node (ref "R20") (pin "2") (pinfunction "2_2") (pintype "passive"))
    )
    (net (code "67") (name "Net-(DS17-A-Pad7)") (class "Default")
      (node (ref "DS17") (pin "7") (pinfunction "A_7") (pintype "passive"))
      (node (ref "DS18") (pin "7") (pinfunction "A_7") (pintype "passive"))
      (node (ref "DS19") (pin "7") (pinfunction "A_7") (pintype "passive"))
      (node (ref "DS20") (pin "7") (pinfunction "A_7") (pintype "passive"))
      (node (ref "DS21") (pin "7") (pinfunction "A_7") (pintype "passive"))
      (node (ref "DS22") (pin "7") (pinfunction "A_7") (pintype "passive"))
      (node (ref "DS23") (pin "7") (pinfunction "A_7") (pintype "passive"))
      (node (ref "R38") (pin "2") (pinfunction "2_2") (pintype "passive"))
    )
    (net (code "68") (name "Net-(DS17-B)") (class "Default")
      (node (ref "DS17") (pin "6") (pinfunction "B_6") (pintype "passive"))
      (node (ref "DS18") (pin "6") (pinfunction "B_6") (pintype "passive"))
      (node (ref "DS19") (pin "6") (pinfunction "B_6") (pintype "passive"))
      (node (ref "DS20") (pin "6") (pinfunction "B_6") (pintype "passive"))
      (node (ref "DS21") (pin "6") (pinfunction "B_6") (pintype "passive"))
      (node (ref "DS22") (pin "6") (pinfunction "B_6") (pintype "passive"))
      (node (ref "DS23") (pin "6") (pinfunction "B_6") (pintype "passive"))
      (node (ref "R39") (pin "2") (pinfunction "2_2") (pintype "passive"))
    )
    (net (code "69") (name "Net-(DS17-C)") (class "Default")
      (node (ref "DS17") (pin "4") (pinfunction "C_4") (pintype "passive"))
      (node (ref "DS18") (pin "4") (pinfunction "C_4") (pintype "passive"))
      (node (ref "DS19") (pin "4") (pinfunction "C_4") (pintype "passive"))
      (node (ref "DS20") (pin "4") (pinfunction "C_4") (pintype "passive"))
      (node (ref "DS21") (pin "4") (pinfunction "C_4") (pintype "passive"))
      (node (ref "DS22") (pin "4") (pinfunction "C_4") (pintype "passive"))
      (node (ref "DS23") (pin "4") (pinfunction "C_4") (pintype "passive"))
      (node (ref "R40") (pin "2") (pinfunction "2_2") (pintype "passive"))
    )
    (net (code "70") (name "Net-(DS17-D)") (class "Default")
      (node (ref "DS17") (pin "2") (pinfunction "D_2") (pintype "passive"))
      (node (ref "DS18") (pin "2") (pinfunction "D_2") (pintype "passive"))
      (node (ref "DS19") (pin "2") (pinfunction "D_2") (pintype "passive"))
      (node (ref "DS20") (pin "2") (pinfunction "D_2") (pintype "passive"))
      (node (ref "DS21") (pin "2") (pinfunction "D_2") (pintype "passive"))
      (node (ref "DS22") (pin "2") (pinfunction "D_2") (pintype "passive"))
      (node (ref "DS23") (pin "2") (pinfunction "D_2") (pintype "passive"))
      (node (ref "R41") (pin "2") (pinfunction "2_2") (pintype "passive"))
    )
    (net (code "71") (name "Net-(DS17-E)") (class "Default")
      (node (ref "DS17") (pin "1") (pinfunction "E_1") (pintype "passive"))
      (node (ref "DS18") (pin "1") (pinfunction "E_1") (pintype "passive"))
      (node (ref "DS19") (pin "1") (pinfunction "E_1") (pintype "passive"))
      (node (ref "DS20") (pin "1") (pinfunction "E_1") (pintype "passive"))
      (node (ref "DS21") (pin "1") (pinfunction "E_1") (pintype "passive"))
      (node (ref "DS22") (pin "1") (pinfunction "E_1") (pintype "passive"))
      (node (ref "DS23") (pin "1") (pinfunction "E_1") (pintype "passive"))
      (node (ref "R42") (pin "2") (pinfunction "2_2") (pintype "passive"))
    )
    (net (code "72") (name "Net-(DS17-F)") (class "Default")
      (node (ref "DS17") (pin "9") (pinfunction "F_9") (pintype "passive"))
      (node (ref "DS18") (pin "9") (pinfunction "F_9") (pintype "passive"))
      (node (ref "DS19") (pin "9") (pinfunction "F_9") (pintype "passive"))
      (node (ref "DS20") (pin "9") (pinfunction "F_9") (pintype "passive"))
      (node (ref "DS21") (pin "9") (pinfunction "F_9") (pintype "passive"))
      (node (ref "DS22") (pin "9") (pinfunction "F_9") (pintype "passive"))
      (node (ref "DS23") (pin "9") (pinfunction "F_9") (pintype "passive"))
      (node (ref "R43") (pin "2") (pinfunction "2_2") (pintype "passive"))
    )
    (net (code "73") (name "Net-(DS17-G)") (class "Default")
      (node (ref "DS17") (pin "10") (pinfunction "G_10") (pintype "passive"))
      (node (ref "DS18") (pin "10") (pinfunction "G_10") (pintype "passive"))
      (node (ref "DS19") (pin "10") (pinfunction "G_10") (pintype "passive"))
      (node (ref "DS20") (pin "10") (pinfunction "G_10") (pintype "passive"))
      (node (ref "DS21") (pin "10") (pinfunction "G_10") (pintype "passive"))
      (node (ref "DS22") (pin "10") (pinfunction "G_10") (pintype "passive"))
      (node (ref "DS23") (pin "10") (pinfunction "G_10") (pintype "passive"))
      (node (ref "R44") (pin "2") (pinfunction "2_2") (pintype "passive"))
    )
    (net (code "74") (name "unconnected-(CPU_RESET-Pad2)") (class "Default")
      (node (ref "CPU_RESET") (pin "2") (pinfunction "2_2") (pintype "passive+no_connect"))
    )
    (net (code "75") (name "unconnected-(CPU_RESET-Pad3)") (class "Default")
      (node (ref "CPU_RESET") (pin "3") (pinfunction "3_3") (pintype "passive+no_connect"))
    )
    (net (code "76") (name "unconnected-(DS17-A-Pad8)") (class "Default")
      (node (ref "DS17") (pin "8") (pinfunction "A_8") (pintype "passive"))
    )
    (net (code "77") (name "unconnected-(DS17-DP-Pad5)") (class "Default")
      (node (ref "DS17") (pin "5") (pinfunction "DP_5") (pintype "passive"))
    )
    (net (code "78") (name "unconnected-(DS18-A-Pad8)") (class "Default")
      (node (ref "DS18") (pin "8") (pinfunction "A_8") (pintype "passive"))
    )
    (net (code "79") (name "unconnected-(DS18-DP-Pad5)") (class "Default")
      (node (ref "DS18") (pin "5") (pinfunction "DP_5") (pintype "passive"))
    )
    (net (code "80") (name "unconnected-(DS19-A-Pad8)") (class "Default")
      (node (ref "DS19") (pin "8") (pinfunction "A_8") (pintype "passive"))
    )
    (net (code "81") (name "unconnected-(DS19-DP-Pad5)") (class "Default")
      (node (ref "DS19") (pin "5") (pinfunction "DP_5") (pintype "passive"))
    )
    (net (code "82") (name "unconnected-(DS20-A-Pad8)") (class "Default")
      (node (ref "DS20") (pin "8") (pinfunction "A_8") (pintype "passive"))
    )
    (net (code "83") (name "unconnected-(DS20-DP-Pad5)") (class "Default")
      (node (ref "DS20") (pin "5") (pinfunction "DP_5") (pintype "passive"))
    )
    (net (code "84") (name "unconnected-(DS21-A-Pad8)") (class "Default")
      (node (ref "DS21") (pin "8") (pinfunction "A_8") (pintype "passive"))
    )
    (net (code "85") (name "unconnected-(DS21-DP-Pad5)") (class "Default")
      (node (ref "DS21") (pin "5") (pinfunction "DP_5") (pintype "passive"))
    )
    (net (code "86") (name "unconnected-(DS22-A-Pad8)") (class "Default")
      (node (ref "DS22") (pin "8") (pinfunction "A_8") (pintype "passive"))
    )
    (net (code "87") (name "unconnected-(DS22-DP-Pad5)") (class "Default")
      (node (ref "DS22") (pin "5") (pinfunction "DP_5") (pintype "passive"))
    )
    (net (code "88") (name "unconnected-(DS23-A-Pad8)") (class "Default")
      (node (ref "DS23") (pin "8") (pinfunction "A_8") (pintype "passive"))
    )
    (net (code "89") (name "unconnected-(DS23-DP-Pad5)") (class "Default")
      (node (ref "DS23") (pin "5") (pinfunction "DP_5") (pintype "passive"))
    )
    (net (code "90") (name "unconnected-(SW2-Pad1)") (class "Default")
      (node (ref "SW2") (pin "1") (pinfunction "1_1") (pintype "passive+no_connect"))
    )
    (net (code "91") (name "unconnected-(SW3-Pad1)") (class "Default")
      (node (ref "SW3") (pin "1") (pinfunction "1_1") (pintype "passive+no_connect"))
    )
    (net (code "92") (name "unconnected-(SW4-Pad1)") (class "Default")
      (node (ref "SW4") (pin "1") (pinfunction "1_1") (pintype "passive+no_connect"))
    )
    (net (code "93") (name "unconnected-(SW5-Pad1)") (class "Default")
      (node (ref "SW5") (pin "1") (pinfunction "1_1") (pintype "passive+no_connect"))
    )
    (net (code "94") (name "unconnected-(SW6-Pad1)") (class "Default")
      (node (ref "SW6") (pin "1") (pinfunction "1_1") (pintype "passive+no_connect"))
    )
    (net (code "95") (name "unconnected-(SW7-Pad1)") (class "Default")
      (node (ref "SW7") (pin "1") (pinfunction "1_1") (pintype "passive+no_connect"))
    )
    (net (code "96") (name "unconnected-(SW8-Pad1)") (class "Default")
      (node (ref "SW8") (pin "1") (pinfunction "1_1") (pintype "passive+no_connect"))
    )
    (net (code "97") (name "unconnected-(SW9-Pad1)") (class "Default")
      (node (ref "SW9") (pin "1") (pinfunction "1_1") (pintype "passive+no_connect"))
    )
    (net (code "98") (name "unconnected-(SW10-Pad1)") (class "Default")
      (node (ref "SW10") (pin "1") (pinfunction "1_1") (pintype "passive+no_connect"))
    )
    (net (code "99") (name "unconnected-(SW11-Pad1)") (class "Default")
      (node (ref "SW11") (pin "1") (pinfunction "1_1") (pintype "passive+no_connect"))
    )
    (net (code "100") (name "unconnected-(SW12-Pad1)") (class "Default")
      (node (ref "SW12") (pin "1") (pinfunction "1_1") (pintype "passive+no_connect"))
    )
    (net (code "101") (name "unconnected-(SW13-Pad1)") (class "Default")
      (node (ref "SW13") (pin "1") (pinfunction "1_1") (pintype "passive+no_connect"))
    )
    (net (code "102") (name "unconnected-(SW14-Pad1)") (class "Default")
      (node (ref "SW14") (pin "1") (pinfunction "1_1") (pintype "passive+no_connect"))
    )
    (net (code "103") (name "unconnected-(SW15-Pad1)") (class "Default")
      (node (ref "SW15") (pin "1") (pinfunction "1_1") (pintype "passive+no_connect"))
    )
    (net (code "104") (name "unconnected-(SW16-Pad1)") (class "Default")
      (node (ref "SW16") (pin "1") (pinfunction "1_1") (pintype "passive+no_connect"))
    )
    (net (code "105") (name "unconnected-(SW17-Pad1)") (class "Default")
      (node (ref "SW17") (pin "1") (pinfunction "1_1") (pintype "passive+no_connect"))
    )
  )
)
